# multi-pcb-cpu.net
KiCad netlist of a schematic drawn in EAGLE
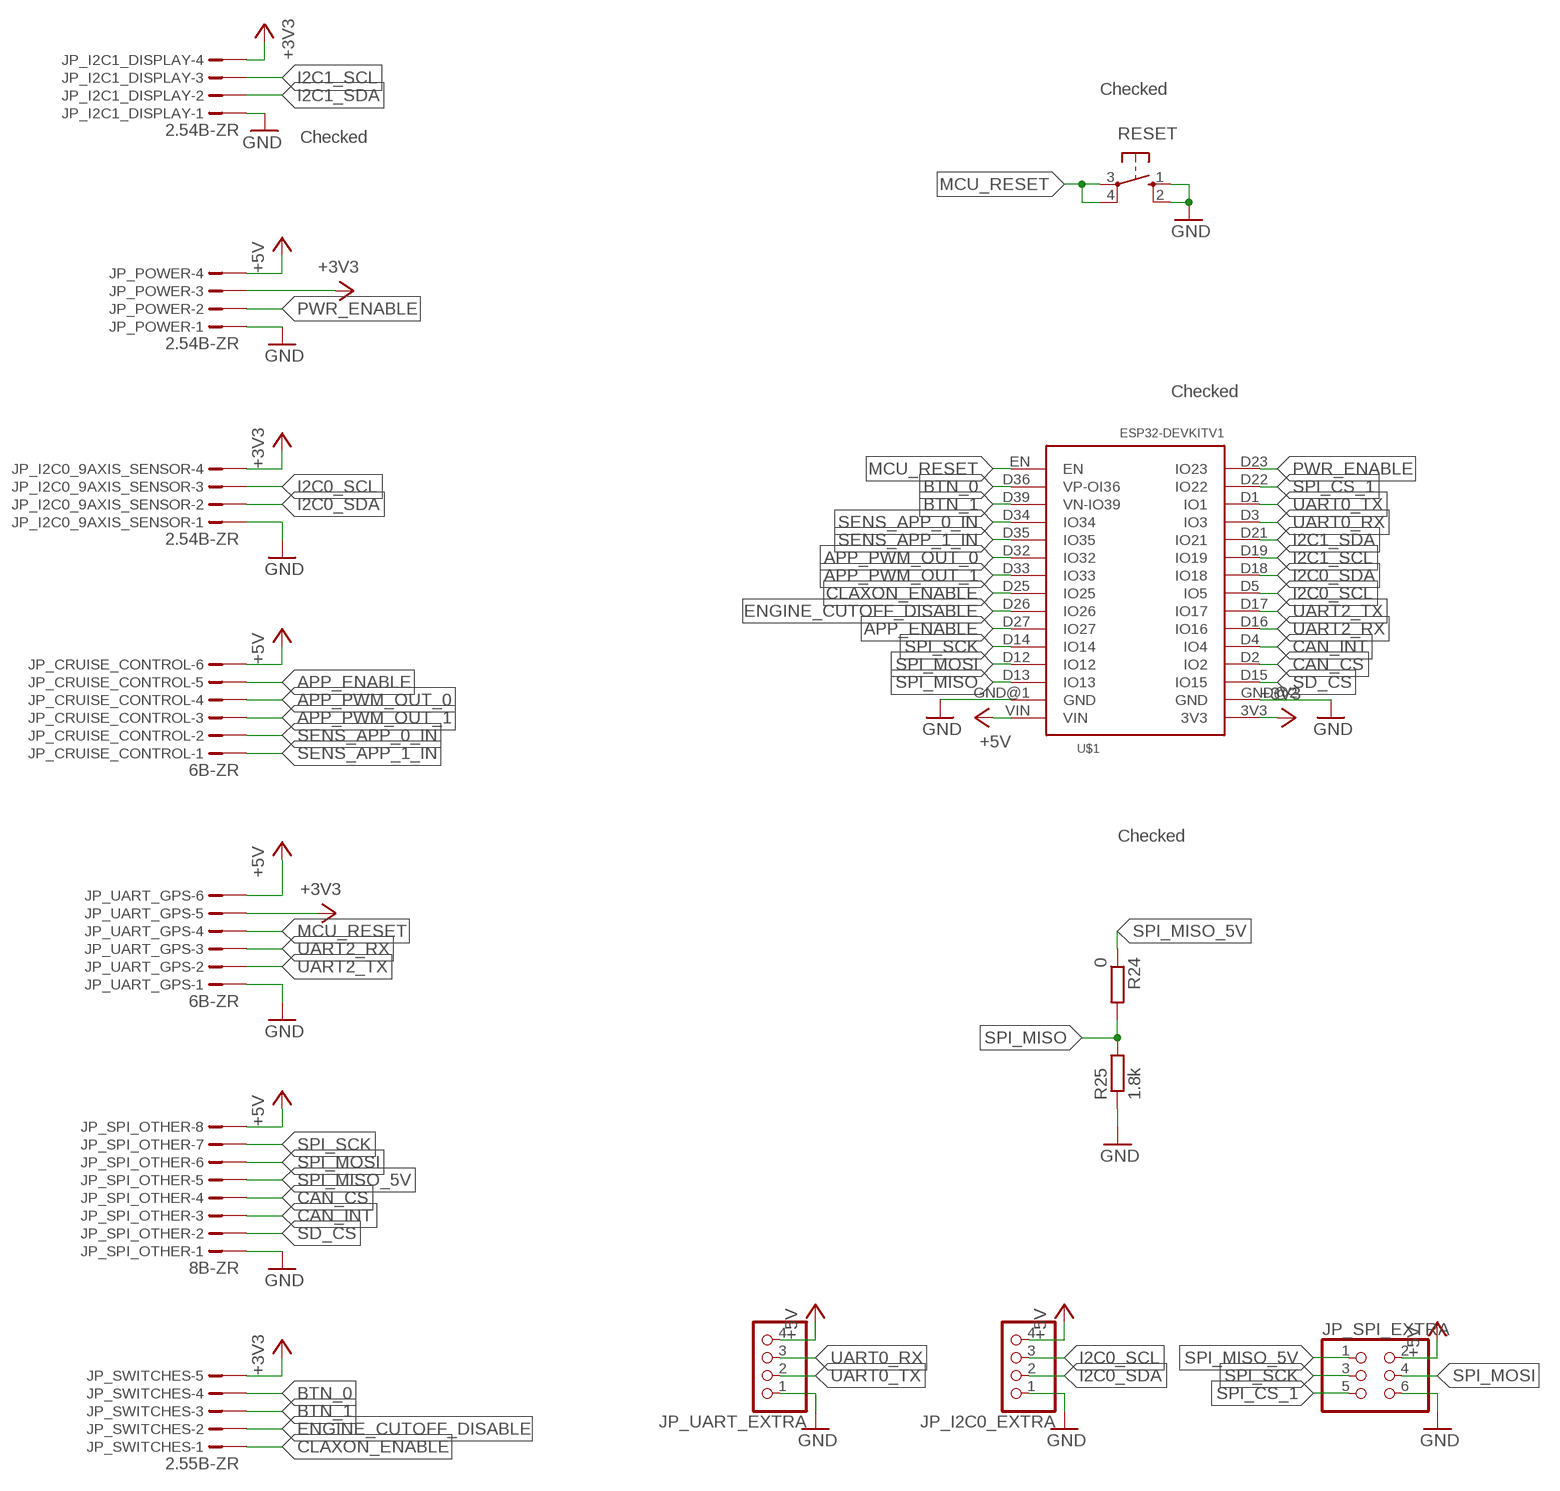
[diagram p0: schematic, sheet 1]

(export (version "E")
  (design (tool "Eeschema 10.0.6"))
  (components
    (comp (ref "JP_CRUISE_CONTROL")
      (value "6B-ZR")
      (footprint "eagle-import:B6B-ZR2.5")
      (libsource (lib "eagle-import") (part "?6B-ZR"))
    )
    (comp (ref "JP_I2C0_9AXIS_SENSOR")
      (value "2.54B-ZR")
      (footprint "eagle-import:B4B-ZR2.5")
      (libsource (lib "eagle-import") (part "?4B-ZR2.5"))
    )
    (comp (ref "JP_I2C0_EXTRA")
      (value "PINHD-1X4")
      (footprint "eagle-import:1X04")
      (libsource (lib "eagle-import") (part "PINHD-1X4"))
    )
    (comp (ref "JP_I2C1_DISPLAY")
      (value "2.54B-ZR")
      (footprint "eagle-import:B4B-ZR2.5")
      (libsource (lib "eagle-import") (part "?4B-ZR2.5"))
    )
    (comp (ref "JP_POWER")
      (value "2.54B-ZR")
      (footprint "eagle-import:B4B-ZR2.5")
      (libsource (lib "eagle-import") (part "?4B-ZR2.5"))
    )
    (comp (ref "JP_SPI_EXTRA")
      (value "PINHD-2X3")
      (footprint "eagle-import:2X03")
      (libsource (lib "eagle-import") (part "PINHD-2X3"))
    )
    (comp (ref "JP_SPI_OTHER")
      (value "8B-ZR")
      (footprint "eagle-import:B8B-ZR2.5")
      (libsource (lib "eagle-import") (part "?8B-ZR"))
    )
    (comp (ref "JP_SWITCHES")
      (value "2.55B-ZR")
      (footprint "eagle-import:B5B-ZR2.5")
      (libsource (lib "eagle-import") (part "?5B-ZR2.5"))
    )
    (comp (ref "JP_UART_EXTRA")
      (value "PINHD-1X4")
      (footprint "eagle-import:1X04")
      (libsource (lib "eagle-import") (part "PINHD-1X4"))
    )
    (comp (ref "JP_UART_GPS")
      (value "6B-ZR")
      (footprint "eagle-import:B6B-ZR2.5")
      (libsource (lib "eagle-import") (part "?6B-ZR"))
    )
    (comp (ref "R24")
      (value "0")
      (footprint "eagle-import:0207_7")
      (libsource (lib "eagle-import") (part "R-EU_0207/7"))
    )
    (comp (ref "R25")
      (value "1.8k")
      (footprint "eagle-import:0207_7")
      (libsource (lib "eagle-import") (part "R-EU_0207/7"))
    )
    (comp (ref "RESET")
      (value "10-XX")
      (footprint "eagle-import:B3F-10XX")
      (fields (field (name "MPN") "B3F-1000"))
      (libsource (lib "eagle-import") (part "10-XX"))
    )
    (comp (ref "U$1")
      (value "ESP32DEVKITV1")
      (footprint "eagle-import:ESP32-DEVKITV1")
      (libsource (lib "eagle-import") (part "ESP32DEVKITV1"))
    )
  )
  (nets
    (net (code "1") (name "+3V3") (class "Default")
      (node (ref "JP_I2C0_9AXIS_SENSOR") (pin "4") (pinfunction "1_4") (pintype "passive"))
      (node (ref "JP_I2C1_DISPLAY") (pin "4") (pinfunction "1_4") (pintype "passive"))
      (node (ref "JP_POWER") (pin "3") (pinfunction "1_3") (pintype "passive"))
      (node (ref "JP_SWITCHES") (pin "5") (pinfunction "1_5") (pintype "passive"))
      (node (ref "JP_UART_GPS") (pin "5") (pinfunction "1_5") (pintype "passive"))
      (node (ref "U$1") (pin "3V3") (pinfunction "3V3_3V3") (pintype "bidirectional"))
    )
    (net (code "2") (name "+5V") (class "Default")
      (node (ref "JP_CRUISE_CONTROL") (pin "6") (pinfunction "1_6") (pintype "passive"))
      (node (ref "JP_I2C0_EXTRA") (pin "4") (pinfunction "4_4") (pintype "passive"))
      (node (ref "JP_POWER") (pin "4") (pinfunction "1_4") (pintype "passive"))
      (node (ref "JP_SPI_EXTRA") (pin "2") (pinfunction "2_2") (pintype "passive"))
      (node (ref "JP_SPI_OTHER") (pin "8") (pinfunction "1_8") (pintype "passive"))
      (node (ref "JP_UART_EXTRA") (pin "4") (pinfunction "4_4") (pintype "passive"))
      (node (ref "JP_UART_GPS") (pin "6") (pinfunction "1_6") (pintype "passive"))
      (node (ref "U$1") (pin "VIN") (pinfunction "VIN_VIN") (pintype "bidirectional"))
    )
    (net (code "3") (name "APP_ENABLE") (class "Default")
      (node (ref "JP_CRUISE_CONTROL") (pin "5") (pinfunction "1_5") (pintype "passive"))
      (node (ref "U$1") (pin "D27") (pinfunction "IO27_D27") (pintype "bidirectional"))
    )
    (net (code "4") (name "APP_PWM_OUT_0") (class "Default")
      (node (ref "JP_CRUISE_CONTROL") (pin "4") (pinfunction "1_4") (pintype "passive"))
      (node (ref "U$1") (pin "D32") (pinfunction "IO32_D32") (pintype "bidirectional"))
    )
    (net (code "5") (name "APP_PWM_OUT_1") (class "Default")
      (node (ref "JP_CRUISE_CONTROL") (pin "3") (pinfunction "1_3") (pintype "passive"))
      (node (ref "U$1") (pin "D33") (pinfunction "IO33_D33") (pintype "bidirectional"))
    )
    (net (code "6") (name "BTN_0") (class "Default")
      (node (ref "JP_SWITCHES") (pin "4") (pinfunction "1_4") (pintype "passive"))
      (node (ref "U$1") (pin "D36") (pinfunction "VP-OI36_D36") (pintype "bidirectional"))
    )
    (net (code "7") (name "BTN_1") (class "Default")
      (node (ref "JP_SWITCHES") (pin "3") (pinfunction "1_3") (pintype "passive"))
      (node (ref "U$1") (pin "D39") (pinfunction "VN-IO39_D39") (pintype "bidirectional"))
    )
    (net (code "8") (name "CAN_CS") (class "Default")
      (node (ref "JP_SPI_OTHER") (pin "4") (pinfunction "1_4") (pintype "passive"))
      (node (ref "U$1") (pin "D2") (pinfunction "IO2_D2") (pintype "bidirectional"))
    )
    (net (code "9") (name "CAN_INT") (class "Default")
      (node (ref "JP_SPI_OTHER") (pin "3") (pinfunction "1_3") (pintype "passive"))
      (node (ref "U$1") (pin "D4") (pinfunction "IO4_D4") (pintype "bidirectional"))
    )
    (net (code "10") (name "CLAXON_ENABLE") (class "Default")
      (node (ref "JP_SWITCHES") (pin "1") (pinfunction "1_1") (pintype "passive"))
      (node (ref "U$1") (pin "D25") (pinfunction "IO25_D25") (pintype "bidirectional"))
    )
    (net (code "11") (name "ENGINE_CUTOFF_DISABLE") (class "Default")
      (node (ref "JP_SWITCHES") (pin "2") (pinfunction "1_2") (pintype "passive"))
      (node (ref "U$1") (pin "D26") (pinfunction "IO26_D26") (pintype "bidirectional"))
    )
    (net (code "12") (name "GND") (class "Default")
      (node (ref "JP_I2C0_9AXIS_SENSOR") (pin "1") (pinfunction "1_1") (pintype "passive"))
      (node (ref "JP_I2C0_EXTRA") (pin "1") (pinfunction "1_1") (pintype "passive"))
      (node (ref "JP_I2C1_DISPLAY") (pin "1") (pinfunction "1_1") (pintype "passive"))
      (node (ref "JP_POWER") (pin "1") (pinfunction "1_1") (pintype "passive"))
      (node (ref "JP_SPI_EXTRA") (pin "6") (pinfunction "6_6") (pintype "passive"))
      (node (ref "JP_SPI_OTHER") (pin "1") (pinfunction "1_1") (pintype "passive"))
      (node (ref "JP_UART_EXTRA") (pin "1") (pinfunction "1_1") (pintype "passive"))
      (node (ref "JP_UART_GPS") (pin "1") (pinfunction "1_1") (pintype "passive"))
      (node (ref "R25") (pin "1") (pinfunction "1_1") (pintype "passive"))
      (node (ref "RESET") (pin "1") (pinfunction "S_1") (pintype "passive"))
      (node (ref "RESET") (pin "2") (pinfunction "S1_2") (pintype "passive"))
      (node (ref "U$1") (pin "GND@1") (pinfunction "GND_GND@1") (pintype "bidirectional"))
      (node (ref "U$1") (pin "GND@2") (pinfunction "GND_GND@2") (pintype "bidirectional"))
    )
    (net (code "13") (name "I2C0_SCL") (class "Default")
      (node (ref "JP_I2C0_9AXIS_SENSOR") (pin "3") (pinfunction "1_3") (pintype "passive"))
      (node (ref "JP_I2C0_EXTRA") (pin "3") (pinfunction "3_3") (pintype "passive"))
      (node (ref "U$1") (pin "D5") (pinfunction "IO5_D5") (pintype "bidirectional"))
    )
    (net (code "14") (name "I2C0_SDA") (class "Default")
      (node (ref "JP_I2C0_9AXIS_SENSOR") (pin "2") (pinfunction "1_2") (pintype "passive"))
      (node (ref "JP_I2C0_EXTRA") (pin "2") (pinfunction "2_2") (pintype "passive"))
      (node (ref "U$1") (pin "D18") (pinfunction "IO18_D18") (pintype "bidirectional"))
    )
    (net (code "15") (name "I2C1_SCL") (class "Default")
      (node (ref "JP_I2C1_DISPLAY") (pin "3") (pinfunction "1_3") (pintype "passive"))
      (node (ref "U$1") (pin "D19") (pinfunction "IO19_D19") (pintype "bidirectional"))
    )
    (net (code "16") (name "I2C1_SDA") (class "Default")
      (node (ref "JP_I2C1_DISPLAY") (pin "2") (pinfunction "1_2") (pintype "passive"))
      (node (ref "U$1") (pin "D21") (pinfunction "IO21_D21") (pintype "bidirectional"))
    )
    (net (code "17") (name "MCU_RESET") (class "Default")
      (node (ref "JP_UART_GPS") (pin "4") (pinfunction "1_4") (pintype "passive"))
      (node (ref "RESET") (pin "3") (pinfunction "P_3") (pintype "passive"))
      (node (ref "RESET") (pin "4") (pinfunction "P1_4") (pintype "passive"))
      (node (ref "U$1") (pin "EN") (pinfunction "EN_EN") (pintype "bidirectional"))
    )
    (net (code "18") (name "PWR_ENABLE") (class "Default")
      (node (ref "JP_POWER") (pin "2") (pinfunction "1_2") (pintype "passive"))
      (node (ref "U$1") (pin "D23") (pinfunction "IO23_D23") (pintype "bidirectional"))
    )
    (net (code "19") (name "SD_CS") (class "Default")
      (node (ref "JP_SPI_OTHER") (pin "2") (pinfunction "1_2") (pintype "passive"))
      (node (ref "U$1") (pin "D15") (pinfunction "IO15_D15") (pintype "bidirectional"))
    )
    (net (code "20") (name "SENS_APP_0_IN") (class "Default")
      (node (ref "JP_CRUISE_CONTROL") (pin "2") (pinfunction "1_2") (pintype "passive"))
      (node (ref "U$1") (pin "D34") (pinfunction "IO34_D34") (pintype "bidirectional"))
    )
    (net (code "21") (name "SENS_APP_1_IN") (class "Default")
      (node (ref "JP_CRUISE_CONTROL") (pin "1") (pinfunction "1_1") (pintype "passive"))
      (node (ref "U$1") (pin "D35") (pinfunction "IO35_D35") (pintype "bidirectional"))
    )
    (net (code "22") (name "SPI_CS_1") (class "Default")
      (node (ref "JP_SPI_EXTRA") (pin "5") (pinfunction "5_5") (pintype "passive"))
      (node (ref "U$1") (pin "D22") (pinfunction "IO22_D22") (pintype "bidirectional"))
    )
    (net (code "23") (name "SPI_MISO") (class "Default")
      (node (ref "R24") (pin "2") (pinfunction "2_2") (pintype "passive"))
      (node (ref "R25") (pin "2") (pinfunction "2_2") (pintype "passive"))
      (node (ref "U$1") (pin "D13") (pinfunction "IO13_D13") (pintype "bidirectional"))
    )
    (net (code "24") (name "SPI_MISO_5V") (class "Default")
      (node (ref "JP_SPI_EXTRA") (pin "1") (pinfunction "1_1") (pintype "passive"))
      (node (ref "JP_SPI_OTHER") (pin "5") (pinfunction "1_5") (pintype "passive"))
      (node (ref "R24") (pin "1") (pinfunction "1_1") (pintype "passive"))
    )
    (net (code "25") (name "SPI_MOSI") (class "Default")
      (node (ref "JP_SPI_EXTRA") (pin "4") (pinfunction "4_4") (pintype "passive"))
      (node (ref "JP_SPI_OTHER") (pin "6") (pinfunction "1_6") (pintype "passive"))
      (node (ref "U$1") (pin "D12") (pinfunction "IO12_D12") (pintype "bidirectional"))
    )
    (net (code "26") (name "SPI_SCK") (class "Default")
      (node (ref "JP_SPI_EXTRA") (pin "3") (pinfunction "3_3") (pintype "passive"))
      (node (ref "JP_SPI_OTHER") (pin "7") (pinfunction "1_7") (pintype "passive"))
      (node (ref "U$1") (pin "D14") (pinfunction "IO14_D14") (pintype "bidirectional"))
    )
    (net (code "27") (name "UART0_RX") (class "Default")
      (node (ref "JP_UART_EXTRA") (pin "3") (pinfunction "3_3") (pintype "passive"))
      (node (ref "U$1") (pin "D3") (pinfunction "IO3_D3") (pintype "bidirectional"))
    )
    (net (code "28") (name "UART0_TX") (class "Default")
      (node (ref "JP_UART_EXTRA") (pin "2") (pinfunction "2_2") (pintype "passive"))
      (node (ref "U$1") (pin "D1") (pinfunction "IO1_D1") (pintype "bidirectional"))
    )
    (net (code "29") (name "UART2_RX") (class "Default")
      (node (ref "JP_UART_GPS") (pin "3") (pinfunction "1_3") (pintype "passive"))
      (node (ref "U$1") (pin "D16") (pinfunction "IO16_D16") (pintype "bidirectional"))
    )
    (net (code "30") (name "UART2_TX") (class "Default")
      (node (ref "JP_UART_GPS") (pin "2") (pinfunction "1_2") (pintype "passive"))
      (node (ref "U$1") (pin "D17") (pinfunction "IO17_D17") (pintype "bidirectional"))
    )
  )
)
